# Sheet1.net
KiCad netlist of a schematic drawn in Altium Designer
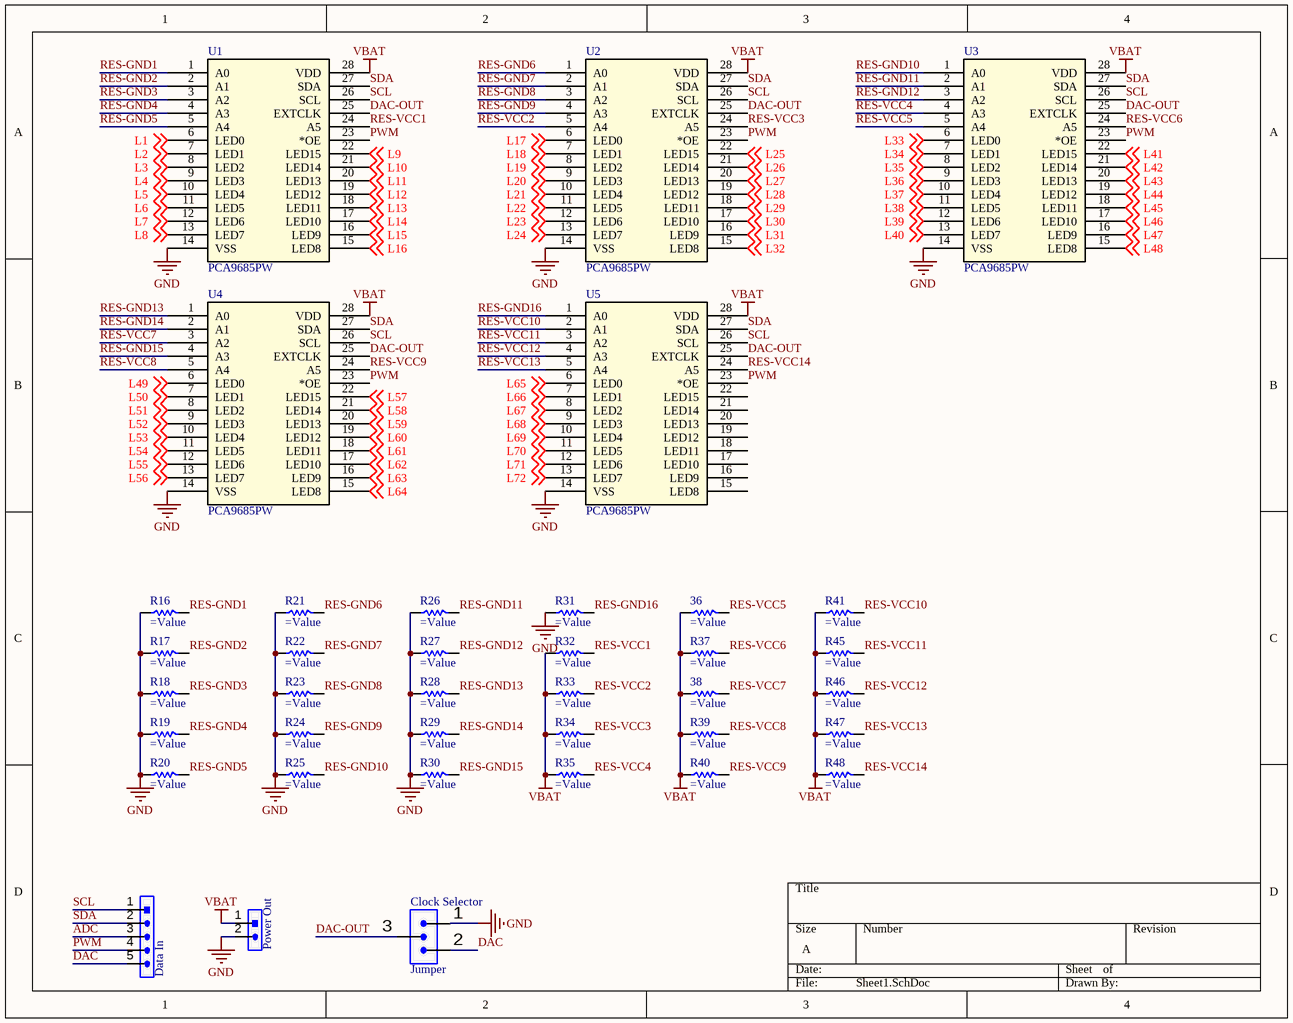
[diagram p0: Sheet1.SchDoc]

(export (version "E")
  (design (tool "Eeschema 10.0.6"))
  (components
    (comp (ref "36")
      (value "~")
      (footprint "R 0805")
      (description "Chip resistor")
      (fields (field (name "版权归属") "源创客"))
      (libsource (lib "Passive (Resistor-Capacitor-Inductor-Veristor-Ferrite)") (part "R"))
    )
    (comp (ref "38")
      (value "~")
      (footprint "R 0805")
      (description "Chip resistor")
      (fields (field (name "版权归属") "源创客"))
      (libsource (lib "Passive (Resistor-Capacitor-Inductor-Veristor-Ferrite)") (part "R"))
    )
    (comp (ref "Clock Selector")
      (value "Jumper")
      (footprint "Jumper Selector")
      (description "Jumper Selector")
      (libsource (lib "Jumper-SolderBridge") (part "Jumper Selector"))
    )
    (comp (ref "Data In")
      (value "HDR-1X5")
      (footprint "XH2.54-5P_H")
      (description "5P Connector")
      (fields (field (name "版权归属") "源创客"))
      (libsource (lib "Connectors") (part "Header 5"))
    )
    (comp (ref "Power Out")
      (value "HDR-1X2")
      (footprint "XH2.54-2P_H")
      (description "2P Connector")
      (fields (field (name "版权归属") "源创客"))
      (libsource (lib "Connectors") (part "Header 2"))
    )
    (comp (ref "R16")
      (value "~")
      (footprint "R 0805")
      (description "Chip resistor")
      (fields (field (name "版权归属") "源创客"))
      (libsource (lib "Passive (Resistor-Capacitor-Inductor-Veristor-Ferrite)") (part "R"))
    )
    (comp (ref "R17")
      (value "~")
      (footprint "R 0805")
      (description "Chip resistor")
      (fields (field (name "版权归属") "源创客"))
      (libsource (lib "Passive (Resistor-Capacitor-Inductor-Veristor-Ferrite)") (part "R"))
    )
    (comp (ref "R18")
      (value "~")
      (footprint "R 0805")
      (description "Chip resistor")
      (fields (field (name "版权归属") "源创客"))
      (libsource (lib "Passive (Resistor-Capacitor-Inductor-Veristor-Ferrite)") (part "R"))
    )
    (comp (ref "R19")
      (value "~")
      (footprint "R 0805")
      (description "Chip resistor")
      (fields (field (name "版权归属") "源创客"))
      (libsource (lib "Passive (Resistor-Capacitor-Inductor-Veristor-Ferrite)") (part "R"))
    )
    (comp (ref "R20")
      (value "~")
      (footprint "R 0805")
      (description "Chip resistor")
      (fields (field (name "版权归属") "源创客"))
      (libsource (lib "Passive (Resistor-Capacitor-Inductor-Veristor-Ferrite)") (part "R"))
    )
    (comp (ref "R21")
      (value "~")
      (footprint "R 0805")
      (description "Chip resistor")
      (fields (field (name "版权归属") "源创客"))
      (libsource (lib "Passive (Resistor-Capacitor-Inductor-Veristor-Ferrite)") (part "R"))
    )
    (comp (ref "R22")
      (value "~")
      (footprint "R 0805")
      (description "Chip resistor")
      (fields (field (name "版权归属") "源创客"))
      (libsource (lib "Passive (Resistor-Capacitor-Inductor-Veristor-Ferrite)") (part "R"))
    )
    (comp (ref "R23")
      (value "~")
      (footprint "R 0805")
      (description "Chip resistor")
      (fields (field (name "版权归属") "源创客"))
      (libsource (lib "Passive (Resistor-Capacitor-Inductor-Veristor-Ferrite)") (part "R"))
    )
    (comp (ref "R24")
      (value "~")
      (footprint "R 0805")
      (description "Chip resistor")
      (fields (field (name "版权归属") "源创客"))
      (libsource (lib "Passive (Resistor-Capacitor-Inductor-Veristor-Ferrite)") (part "R"))
    )
    (comp (ref "R25")
      (value "~")
      (footprint "R 0805")
      (description "Chip resistor")
      (fields (field (name "版权归属") "源创客"))
      (libsource (lib "Passive (Resistor-Capacitor-Inductor-Veristor-Ferrite)") (part "R"))
    )
    (comp (ref "R26")
      (value "~")
      (footprint "R 0805")
      (description "Chip resistor")
      (fields (field (name "版权归属") "源创客"))
      (libsource (lib "Passive (Resistor-Capacitor-Inductor-Veristor-Ferrite)") (part "R"))
    )
    (comp (ref "R27")
      (value "~")
      (footprint "R 0805")
      (description "Chip resistor")
      (fields (field (name "版权归属") "源创客"))
      (libsource (lib "Passive (Resistor-Capacitor-Inductor-Veristor-Ferrite)") (part "R"))
    )
    (comp (ref "R28")
      (value "~")
      (footprint "R 0805")
      (description "Chip resistor")
      (fields (field (name "版权归属") "源创客"))
      (libsource (lib "Passive (Resistor-Capacitor-Inductor-Veristor-Ferrite)") (part "R"))
    )
    (comp (ref "R29")
      (value "~")
      (footprint "R 0805")
      (description "Chip resistor")
      (fields (field (name "版权归属") "源创客"))
      (libsource (lib "Passive (Resistor-Capacitor-Inductor-Veristor-Ferrite)") (part "R"))
    )
    (comp (ref "R30")
      (value "~")
      (footprint "R 0805")
      (description "Chip resistor")
      (fields (field (name "版权归属") "源创客"))
      (libsource (lib "Passive (Resistor-Capacitor-Inductor-Veristor-Ferrite)") (part "R"))
    )
    (comp (ref "R31")
      (value "~")
      (footprint "R 0805")
      (description "Chip resistor")
      (fields (field (name "版权归属") "源创客"))
      (libsource (lib "Passive (Resistor-Capacitor-Inductor-Veristor-Ferrite)") (part "R"))
    )
    (comp (ref "R32")
      (value "~")
      (footprint "R 0805")
      (description "Chip resistor")
      (fields (field (name "版权归属") "源创客"))
      (libsource (lib "Passive (Resistor-Capacitor-Inductor-Veristor-Ferrite)") (part "R"))
    )
    (comp (ref "R33")
      (value "~")
      (footprint "R 0805")
      (description "Chip resistor")
      (fields (field (name "版权归属") "源创客"))
      (libsource (lib "Passive (Resistor-Capacitor-Inductor-Veristor-Ferrite)") (part "R"))
    )
    (comp (ref "R34")
      (value "~")
      (footprint "R 0805")
      (description "Chip resistor")
      (fields (field (name "版权归属") "源创客"))
      (libsource (lib "Passive (Resistor-Capacitor-Inductor-Veristor-Ferrite)") (part "R"))
    )
    (comp (ref "R35")
      (value "~")
      (footprint "R 0805")
      (description "Chip resistor")
      (fields (field (name "版权归属") "源创客"))
      (libsource (lib "Passive (Resistor-Capacitor-Inductor-Veristor-Ferrite)") (part "R"))
    )
    (comp (ref "R37")
      (value "~")
      (footprint "R 0805")
      (description "Chip resistor")
      (fields (field (name "版权归属") "源创客"))
      (libsource (lib "Passive (Resistor-Capacitor-Inductor-Veristor-Ferrite)") (part "R"))
    )
    (comp (ref "R39")
      (value "~")
      (footprint "R 0805")
      (description "Chip resistor")
      (fields (field (name "版权归属") "源创客"))
      (libsource (lib "Passive (Resistor-Capacitor-Inductor-Veristor-Ferrite)") (part "R"))
    )
    (comp (ref "R40")
      (value "~")
      (footprint "R 0805")
      (description "Chip resistor")
      (fields (field (name "版权归属") "源创客"))
      (libsource (lib "Passive (Resistor-Capacitor-Inductor-Veristor-Ferrite)") (part "R"))
    )
    (comp (ref "R41")
      (value "~")
      (footprint "R 0805")
      (description "Chip resistor")
      (fields (field (name "版权归属") "源创客"))
      (libsource (lib "Passive (Resistor-Capacitor-Inductor-Veristor-Ferrite)") (part "R"))
    )
    (comp (ref "R45")
      (value "~")
      (footprint "R 0805")
      (description "Chip resistor")
      (fields (field (name "版权归属") "源创客"))
      (libsource (lib "Passive (Resistor-Capacitor-Inductor-Veristor-Ferrite)") (part "R"))
    )
    (comp (ref "R46")
      (value "~")
      (footprint "R 0805")
      (description "Chip resistor")
      (fields (field (name "版权归属") "源创客"))
      (libsource (lib "Passive (Resistor-Capacitor-Inductor-Veristor-Ferrite)") (part "R"))
    )
    (comp (ref "R47")
      (value "~")
      (footprint "R 0805")
      (description "Chip resistor")
      (fields (field (name "版权归属") "源创客"))
      (libsource (lib "Passive (Resistor-Capacitor-Inductor-Veristor-Ferrite)") (part "R"))
    )
    (comp (ref "R48")
      (value "~")
      (footprint "R 0805")
      (description "Chip resistor")
      (fields (field (name "版权归属") "源创客"))
      (libsource (lib "Passive (Resistor-Capacitor-Inductor-Veristor-Ferrite)") (part "R"))
    )
    (comp (ref "U1")
      (value "PCA9685PW")
      (footprint "SOT361-1_NXP")
      (description "No Description Available")
      (fields (field (name "COPYRIGHT") "Copyright (C) 2018 Accelerated Designs. All rights reserved"))
      (libsource (lib "PCA9685") (part "PCA9685PW"))
    )
    (comp (ref "U2")
      (value "PCA9685PW")
      (footprint "SOT361-1_NXP")
      (description "No Description Available")
      (fields (field (name "COPYRIGHT") "Copyright (C) 2018 Accelerated Designs. All rights reserved"))
      (libsource (lib "PCA9685") (part "PCA9685PW"))
    )
    (comp (ref "U3")
      (value "PCA9685PW")
      (footprint "SOT361-1_NXP")
      (description "No Description Available")
      (fields (field (name "COPYRIGHT") "Copyright (C) 2018 Accelerated Designs. All rights reserved"))
      (libsource (lib "PCA9685") (part "PCA9685PW"))
    )
    (comp (ref "U4")
      (value "PCA9685PW")
      (footprint "SOT361-1_NXP")
      (description "No Description Available")
      (fields (field (name "COPYRIGHT") "Copyright (C) 2018 Accelerated Designs. All rights reserved"))
      (libsource (lib "PCA9685") (part "PCA9685PW"))
    )
    (comp (ref "U5")
      (value "PCA9685PW")
      (footprint "SOT361-1_NXP")
      (description "No Description Available")
      (fields (field (name "COPYRIGHT") "Copyright (C) 2018 Accelerated Designs. All rights reserved"))
      (libsource (lib "PCA9685") (part "PCA9685PW"))
    )
  )
  (nets
    (net (code "1") (name "/ADC") (class "Default") (node (ref "Data In") (pin "3") (pintype "passive")))
    (net (code "2") (name "/DAC") (class "Default") (node (ref "Data In") (pin "5") (pintype "passive")))
    (net (code "3") (name "/DAC-OUT") (class "Default")
      (node (ref "Clock Selector") (pin "3") (pinfunction "IN_3") (pintype "passive"))
      (node (ref "U1") (pin "25") (pinfunction "EXTCLK_25") (pintype "passive"))
      (node (ref "U2") (pin "25") (pinfunction "EXTCLK_25") (pintype "passive"))
      (node (ref "U3") (pin "25") (pinfunction "EXTCLK_25") (pintype "passive"))
      (node (ref "U4") (pin "25") (pinfunction "EXTCLK_25") (pintype "passive"))
      (node (ref "U5") (pin "25") (pinfunction "EXTCLK_25") (pintype "passive"))
    )
    (net (code "4") (name "/PWM") (class "Default")
      (node (ref "Data In") (pin "4") (pintype "passive"))
      (node (ref "U1") (pin "23") (pinfunction "*OE_23") (pintype "passive"))
      (node (ref "U2") (pin "23") (pinfunction "*OE_23") (pintype "passive"))
      (node (ref "U3") (pin "23") (pinfunction "*OE_23") (pintype "passive"))
      (node (ref "U4") (pin "23") (pinfunction "*OE_23") (pintype "passive"))
      (node (ref "U5") (pin "23") (pinfunction "*OE_23") (pintype "passive"))
    )
    (net (code "5") (name "/RES-GND1") (class "Default")
      (node (ref "R16") (pin "2") (pinfunction "2_2") (pintype "passive"))
      (node (ref "U1") (pin "1") (pinfunction "A0_1") (pintype "passive"))
    )
    (net (code "6") (name "/RES-GND2") (class "Default")
      (node (ref "R17") (pin "2") (pinfunction "2_2") (pintype "passive"))
      (node (ref "U1") (pin "2") (pinfunction "A1_2") (pintype "passive"))
    )
    (net (code "7") (name "/RES-GND3") (class "Default")
      (node (ref "R18") (pin "2") (pinfunction "2_2") (pintype "passive"))
      (node (ref "U1") (pin "3") (pinfunction "A2_3") (pintype "passive"))
    )
    (net (code "8") (name "/RES-GND4") (class "Default")
      (node (ref "R19") (pin "2") (pinfunction "2_2") (pintype "passive"))
      (node (ref "U1") (pin "4") (pinfunction "A3_4") (pintype "passive"))
    )
    (net (code "9") (name "/RES-GND5") (class "Default")
      (node (ref "R20") (pin "2") (pinfunction "2_2") (pintype "passive"))
      (node (ref "U1") (pin "5") (pinfunction "A4_5") (pintype "passive"))
    )
    (net (code "10") (name "/RES-GND6") (class "Default")
      (node (ref "R21") (pin "2") (pinfunction "2_2") (pintype "passive"))
      (node (ref "U2") (pin "1") (pinfunction "A0_1") (pintype "passive"))
    )
    (net (code "11") (name "/RES-GND7") (class "Default")
      (node (ref "R22") (pin "2") (pinfunction "2_2") (pintype "passive"))
      (node (ref "U2") (pin "2") (pinfunction "A1_2") (pintype "passive"))
    )
    (net (code "12") (name "/RES-GND8") (class "Default")
      (node (ref "R23") (pin "2") (pinfunction "2_2") (pintype "passive"))
      (node (ref "U2") (pin "3") (pinfunction "A2_3") (pintype "passive"))
    )
    (net (code "13") (name "/RES-GND9") (class "Default")
      (node (ref "R24") (pin "2") (pinfunction "2_2") (pintype "passive"))
      (node (ref "U2") (pin "4") (pinfunction "A3_4") (pintype "passive"))
    )
    (net (code "14") (name "/RES-GND10") (class "Default")
      (node (ref "R25") (pin "2") (pinfunction "2_2") (pintype "passive"))
      (node (ref "U3") (pin "1") (pinfunction "A0_1") (pintype "passive"))
    )
    (net (code "15") (name "/RES-GND11") (class "Default")
      (node (ref "R26") (pin "2") (pinfunction "2_2") (pintype "passive"))
      (node (ref "U3") (pin "2") (pinfunction "A1_2") (pintype "passive"))
    )
    (net (code "16") (name "/RES-GND12") (class "Default")
      (node (ref "R27") (pin "2") (pinfunction "2_2") (pintype "passive"))
      (node (ref "U3") (pin "3") (pinfunction "A2_3") (pintype "passive"))
    )
    (net (code "17") (name "/RES-GND13") (class "Default")
      (node (ref "R28") (pin "2") (pinfunction "2_2") (pintype "passive"))
      (node (ref "U4") (pin "1") (pinfunction "A0_1") (pintype "passive"))
    )
    (net (code "18") (name "/RES-GND14") (class "Default")
      (node (ref "R29") (pin "2") (pinfunction "2_2") (pintype "passive"))
      (node (ref "U4") (pin "2") (pinfunction "A1_2") (pintype "passive"))
    )
    (net (code "19") (name "/RES-GND15") (class "Default")
      (node (ref "R30") (pin "2") (pinfunction "2_2") (pintype "passive"))
      (node (ref "U4") (pin "4") (pinfunction "A3_4") (pintype "passive"))
    )
    (net (code "20") (name "/RES-GND16") (class "Default")
      (node (ref "R31") (pin "2") (pinfunction "2_2") (pintype "passive"))
      (node (ref "U5") (pin "1") (pinfunction "A0_1") (pintype "passive"))
    )
    (net (code "21") (name "/RES-VCC1") (class "Default")
      (node (ref "R32") (pin "2") (pinfunction "2_2") (pintype "passive"))
      (node (ref "U1") (pin "24") (pinfunction "A5_24") (pintype "passive"))
    )
    (net (code "22") (name "/RES-VCC2") (class "Default")
      (node (ref "R33") (pin "2") (pinfunction "2_2") (pintype "passive"))
      (node (ref "U2") (pin "5") (pinfunction "A4_5") (pintype "passive"))
    )
    (net (code "23") (name "/RES-VCC3") (class "Default")
      (node (ref "R34") (pin "2") (pinfunction "2_2") (pintype "passive"))
      (node (ref "U2") (pin "24") (pinfunction "A5_24") (pintype "passive"))
    )
    (net (code "24") (name "/RES-VCC4") (class "Default")
      (node (ref "R35") (pin "2") (pinfunction "2_2") (pintype "passive"))
      (node (ref "U3") (pin "4") (pinfunction "A3_4") (pintype "passive"))
    )
    (net (code "25") (name "/RES-VCC5") (class "Default")
      (node (ref "36") (pin "2") (pinfunction "2_2") (pintype "passive"))
      (node (ref "U3") (pin "5") (pinfunction "A4_5") (pintype "passive"))
    )
    (net (code "26") (name "/RES-VCC6") (class "Default")
      (node (ref "R37") (pin "2") (pinfunction "2_2") (pintype "passive"))
      (node (ref "U3") (pin "24") (pinfunction "A5_24") (pintype "passive"))
    )
    (net (code "27") (name "/RES-VCC7") (class "Default")
      (node (ref "38") (pin "2") (pinfunction "2_2") (pintype "passive"))
      (node (ref "U4") (pin "3") (pinfunction "A2_3") (pintype "passive"))
    )
    (net (code "28") (name "/RES-VCC8") (class "Default")
      (node (ref "R39") (pin "2") (pinfunction "2_2") (pintype "passive"))
      (node (ref "U4") (pin "5") (pinfunction "A4_5") (pintype "passive"))
    )
    (net (code "29") (name "/RES-VCC9") (class "Default")
      (node (ref "R40") (pin "2") (pinfunction "2_2") (pintype "passive"))
      (node (ref "U4") (pin "24") (pinfunction "A5_24") (pintype "passive"))
    )
    (net (code "30") (name "/RES-VCC10") (class "Default")
      (node (ref "R41") (pin "2") (pinfunction "2_2") (pintype "passive"))
      (node (ref "U5") (pin "2") (pinfunction "A1_2") (pintype "passive"))
    )
    (net (code "31") (name "/RES-VCC11") (class "Default")
      (node (ref "R45") (pin "2") (pinfunction "2_2") (pintype "passive"))
      (node (ref "U5") (pin "3") (pinfunction "A2_3") (pintype "passive"))
    )
    (net (code "32") (name "/RES-VCC12") (class "Default")
      (node (ref "R46") (pin "2") (pinfunction "2_2") (pintype "passive"))
      (node (ref "U5") (pin "4") (pinfunction "A3_4") (pintype "passive"))
    )
    (net (code "33") (name "/RES-VCC13") (class "Default")
      (node (ref "R47") (pin "2") (pinfunction "2_2") (pintype "passive"))
      (node (ref "U5") (pin "5") (pinfunction "A4_5") (pintype "passive"))
    )
    (net (code "34") (name "/RES-VCC14") (class "Default")
      (node (ref "R48") (pin "2") (pinfunction "2_2") (pintype "passive"))
      (node (ref "U5") (pin "24") (pinfunction "A5_24") (pintype "passive"))
    )
    (net (code "35") (name "/SCL") (class "Default")
      (node (ref "Data In") (pin "1") (pintype "passive"))
      (node (ref "U1") (pin "26") (pinfunction "SCL_26") (pintype "passive"))
      (node (ref "U2") (pin "26") (pinfunction "SCL_26") (pintype "passive"))
      (node (ref "U3") (pin "26") (pinfunction "SCL_26") (pintype "passive"))
      (node (ref "U4") (pin "26") (pinfunction "SCL_26") (pintype "passive"))
      (node (ref "U5") (pin "26") (pinfunction "SCL_26") (pintype "passive"))
    )
    (net (code "36") (name "/SDA") (class "Default")
      (node (ref "Data In") (pin "2") (pintype "passive"))
      (node (ref "U1") (pin "27") (pinfunction "SDA_27") (pintype "passive"))
      (node (ref "U2") (pin "27") (pinfunction "SDA_27") (pintype "passive"))
      (node (ref "U3") (pin "27") (pinfunction "SDA_27") (pintype "passive"))
      (node (ref "U4") (pin "27") (pinfunction "SDA_27") (pintype "passive"))
      (node (ref "U5") (pin "27") (pinfunction "SDA_27") (pintype "passive"))
    )
    (net (code "37") (name "GND") (class "Default")
      (node (ref "Clock Selector") (pin "1") (pinfunction "IN_1") (pintype "passive"))
      (node (ref "Power Out") (pin "2") (pintype "passive"))
      (node (ref "R16") (pin "1") (pinfunction "1_1") (pintype "passive"))
      (node (ref "R17") (pin "1") (pinfunction "1_1") (pintype "passive"))
      (node (ref "R18") (pin "1") (pinfunction "1_1") (pintype "passive"))
      (node (ref "R19") (pin "1") (pinfunction "1_1") (pintype "passive"))
      (node (ref "R20") (pin "1") (pinfunction "1_1") (pintype "passive"))
      (node (ref "R21") (pin "1") (pinfunction "1_1") (pintype "passive"))
      (node (ref "R22") (pin "1") (pinfunction "1_1") (pintype "passive"))
      (node (ref "R23") (pin "1") (pinfunction "1_1") (pintype "passive"))
      (node (ref "R24") (pin "1") (pinfunction "1_1") (pintype "passive"))
      (node (ref "R25") (pin "1") (pinfunction "1_1") (pintype "passive"))
      (node (ref "R26") (pin "1") (pinfunction "1_1") (pintype "passive"))
      (node (ref "R27") (pin "1") (pinfunction "1_1") (pintype "passive"))
      (node (ref "R28") (pin "1") (pinfunction "1_1") (pintype "passive"))
      (node (ref "R29") (pin "1") (pinfunction "1_1") (pintype "passive"))
      (node (ref "R30") (pin "1") (pinfunction "1_1") (pintype "passive"))
      (node (ref "R31") (pin "1") (pinfunction "1_1") (pintype "passive"))
      (node (ref "U1") (pin "14") (pinfunction "VSS_14") (pintype "passive"))
      (node (ref "U2") (pin "14") (pinfunction "VSS_14") (pintype "passive"))
      (node (ref "U3") (pin "14") (pinfunction "VSS_14") (pintype "passive"))
      (node (ref "U4") (pin "14") (pinfunction "VSS_14") (pintype "passive"))
      (node (ref "U5") (pin "14") (pinfunction "VSS_14") (pintype "passive"))
    )
    (net (code "38") (name "L1") (class "Default")
      (node (ref "U1") (pin "6") (pinfunction "LED0_6") (pintype "passive"))
    )
    (net (code "39") (name "L2") (class "Default")
      (node (ref "U1") (pin "7") (pinfunction "LED1_7") (pintype "passive"))
    )
    (net (code "40") (name "L3") (class "Default")
      (node (ref "U1") (pin "8") (pinfunction "LED2_8") (pintype "passive"))
    )
    (net (code "41") (name "L4") (class "Default")
      (node (ref "U1") (pin "9") (pinfunction "LED3_9") (pintype "passive"))
    )
    (net (code "42") (name "L5") (class "Default")
      (node (ref "U1") (pin "10") (pinfunction "LED4_10") (pintype "passive"))
    )
    (net (code "43") (name "L6") (class "Default")
      (node (ref "U1") (pin "11") (pinfunction "LED5_11") (pintype "passive"))
    )
    (net (code "44") (name "L7") (class "Default")
      (node (ref "U1") (pin "12") (pinfunction "LED6_12") (pintype "passive"))
    )
    (net (code "45") (name "L8") (class "Default")
      (node (ref "U1") (pin "13") (pinfunction "LED7_13") (pintype "passive"))
    )
    (net (code "46") (name "L9") (class "Default")
      (node (ref "U1") (pin "22") (pinfunction "LED15_22") (pintype "passive"))
    )
    (net (code "47") (name "L10") (class "Default")
      (node (ref "U1") (pin "21") (pinfunction "LED14_21") (pintype "passive"))
    )
    (net (code "48") (name "L11") (class "Default")
      (node (ref "U1") (pin "20") (pinfunction "LED13_20") (pintype "passive"))
    )
    (net (code "49") (name "L12") (class "Default")
      (node (ref "U1") (pin "19") (pinfunction "LED12_19") (pintype "passive"))
    )
    (net (code "50") (name "L13") (class "Default")
      (node (ref "U1") (pin "18") (pinfunction "LED11_18") (pintype "passive"))
    )
    (net (code "51") (name "L14") (class "Default")
      (node (ref "U1") (pin "17") (pinfunction "LED10_17") (pintype "passive"))
    )
    (net (code "52") (name "L15") (class "Default")
      (node (ref "U1") (pin "16") (pinfunction "LED9_16") (pintype "passive"))
    )
    (net (code "53") (name "L16") (class "Default")
      (node (ref "U1") (pin "15") (pinfunction "LED8_15") (pintype "passive"))
    )
    (net (code "54") (name "L17") (class "Default")
      (node (ref "U2") (pin "6") (pinfunction "LED0_6") (pintype "passive"))
    )
    (net (code "55") (name "L18") (class "Default")
      (node (ref "U2") (pin "7") (pinfunction "LED1_7") (pintype "passive"))
    )
    (net (code "56") (name "L19") (class "Default")
      (node (ref "U2") (pin "8") (pinfunction "LED2_8") (pintype "passive"))
    )
    (net (code "57") (name "L20") (class "Default")
      (node (ref "U2") (pin "9") (pinfunction "LED3_9") (pintype "passive"))
    )
    (net (code "58") (name "L21") (class "Default")
      (node (ref "U2") (pin "10") (pinfunction "LED4_10") (pintype "passive"))
    )
    (net (code "59") (name "L22") (class "Default")
      (node (ref "U2") (pin "11") (pinfunction "LED5_11") (pintype "passive"))
    )
    (net (code "60") (name "L23") (class "Default")
      (node (ref "U2") (pin "12") (pinfunction "LED6_12") (pintype "passive"))
    )
    (net (code "61") (name "L24") (class "Default")
      (node (ref "U2") (pin "13") (pinfunction "LED7_13") (pintype "passive"))
    )
    (net (code "62") (name "L25") (class "Default")
      (node (ref "U2") (pin "22") (pinfunction "LED15_22") (pintype "passive"))
    )
    (net (code "63") (name "L26") (class "Default")
      (node (ref "U2") (pin "21") (pinfunction "LED14_21") (pintype "passive"))
    )
    (net (code "64") (name "L27") (class "Default")
      (node (ref "U2") (pin "20") (pinfunction "LED13_20") (pintype "passive"))
    )
    (net (code "65") (name "L28") (class "Default")
      (node (ref "U2") (pin "19") (pinfunction "LED12_19") (pintype "passive"))
    )
    (net (code "66") (name "L29") (class "Default")
      (node (ref "U2") (pin "18") (pinfunction "LED11_18") (pintype "passive"))
    )
    (net (code "67") (name "L30") (class "Default")
      (node (ref "U2") (pin "17") (pinfunction "LED10_17") (pintype "passive"))
    )
    (net (code "68") (name "L31") (class "Default")
      (node (ref "U2") (pin "16") (pinfunction "LED9_16") (pintype "passive"))
    )
    (net (code "69") (name "L32") (class "Default")
      (node (ref "U2") (pin "15") (pinfunction "LED8_15") (pintype "passive"))
    )
    (net (code "70") (name "L33") (class "Default")
      (node (ref "U3") (pin "6") (pinfunction "LED0_6") (pintype "passive"))
    )
    (net (code "71") (name "L34") (class "Default")
      (node (ref "U3") (pin "7") (pinfunction "LED1_7") (pintype "passive"))
    )
    (net (code "72") (name "L35") (class "Default")
      (node (ref "U3") (pin "8") (pinfunction "LED2_8") (pintype "passive"))
    )
    (net (code "73") (name "L36") (class "Default")
      (node (ref "U3") (pin "9") (pinfunction "LED3_9") (pintype "passive"))
    )
    (net (code "74") (name "L37") (class "Default")
      (node (ref "U3") (pin "10") (pinfunction "LED4_10") (pintype "passive"))
    )
    (net (code "75") (name "L38") (class "Default")
      (node (ref "U3") (pin "11") (pinfunction "LED5_11") (pintype "passive"))
    )
    (net (code "76") (name "L39") (class "Default")
      (node (ref "U3") (pin "12") (pinfunction "LED6_12") (pintype "passive"))
    )
    (net (code "77") (name "L40") (class "Default")
      (node (ref "U3") (pin "13") (pinfunction "LED7_13") (pintype "passive"))
    )
    (net (code "78") (name "L41") (class "Default")
      (node (ref "U3") (pin "22") (pinfunction "LED15_22") (pintype "passive"))
    )
    (net (code "79") (name "L42") (class "Default")
      (node (ref "U3") (pin "21") (pinfunction "LED14_21") (pintype "passive"))
    )
    (net (code "80") (name "L43") (class "Default")
      (node (ref "U3") (pin "20") (pinfunction "LED13_20") (pintype "passive"))
    )
    (net (code "81") (name "L44") (class "Default")
      (node (ref "U3") (pin "19") (pinfunction "LED12_19") (pintype "passive"))
    )
    (net (code "82") (name "L45") (class "Default")
      (node (ref "U3") (pin "18") (pinfunction "LED11_18") (pintype "passive"))
    )
    (net (code "83") (name "L46") (class "Default")
      (node (ref "U3") (pin "17") (pinfunction "LED10_17") (pintype "passive"))
    )
    (net (code "84") (name "L47") (class "Default")
      (node (ref "U3") (pin "16") (pinfunction "LED9_16") (pintype "passive"))
    )
    (net (code "85") (name "L48") (class "Default")
      (node (ref "U3") (pin "15") (pinfunction "LED8_15") (pintype "passive"))
    )
    (net (code "86") (name "L49") (class "Default")
      (node (ref "U4") (pin "6") (pinfunction "LED0_6") (pintype "passive"))
    )
    (net (code "87") (name "L50") (class "Default")
      (node (ref "U4") (pin "7") (pinfunction "LED1_7") (pintype "passive"))
    )
    (net (code "88") (name "L51") (class "Default")
      (node (ref "U4") (pin "8") (pinfunction "LED2_8") (pintype "passive"))
    )
    (net (code "89") (name "L52") (class "Default")
      (node (ref "U4") (pin "9") (pinfunction "LED3_9") (pintype "passive"))
    )
    (net (code "90") (name "L53") (class "Default")
      (node (ref "U4") (pin "10") (pinfunction "LED4_10") (pintype "passive"))
    )
    (net (code "91") (name "L54") (class "Default")
      (node (ref "U4") (pin "11") (pinfunction "LED5_11") (pintype "passive"))
    )
    (net (code "92") (name "L55") (class "Default")
      (node (ref "U4") (pin "12") (pinfunction "LED6_12") (pintype "passive"))
    )
    (net (code "93") (name "L56") (class "Default")
      (node (ref "U4") (pin "13") (pinfunction "LED7_13") (pintype "passive"))
    )
    (net (code "94") (name "L57") (class "Default")
      (node (ref "U4") (pin "22") (pinfunction "LED15_22") (pintype "passive"))
    )
    (net (code "95") (name "L58") (class "Default")
      (node (ref "U4") (pin "21") (pinfunction "LED14_21") (pintype "passive"))
    )
    (net (code "96") (name "L59") (class "Default")
      (node (ref "U4") (pin "20") (pinfunction "LED13_20") (pintype "passive"))
    )
    (net (code "97") (name "L60") (class "Default")
      (node (ref "U4") (pin "19") (pinfunction "LED12_19") (pintype "passive"))
    )
    (net (code "98") (name "L61") (class "Default")
      (node (ref "U4") (pin "18") (pinfunction "LED11_18") (pintype "passive"))
    )
    (net (code "99") (name "L62") (class "Default")
      (node (ref "U4") (pin "17") (pinfunction "LED10_17") (pintype "passive"))
    )
    (net (code "100") (name "L63") (class "Default")
      (node (ref "U4") (pin "16") (pinfunction "LED9_16") (pintype "passive"))
    )
    (net (code "101") (name "L64") (class "Default")
      (node (ref "U4") (pin "15") (pinfunction "LED8_15") (pintype "passive"))
    )
    (net (code "102") (name "L65") (class "Default")
      (node (ref "U5") (pin "6") (pinfunction "LED0_6") (pintype "passive"))
    )
    (net (code "103") (name "L66") (class "Default")
      (node (ref "U5") (pin "7") (pinfunction "LED1_7") (pintype "passive"))
    )
    (net (code "104") (name "L67") (class "Default")
      (node (ref "U5") (pin "8") (pinfunction "LED2_8") (pintype "passive"))
    )
    (net (code "105") (name "L68") (class "Default")
      (node (ref "U5") (pin "9") (pinfunction "LED3_9") (pintype "passive"))
    )
    (net (code "106") (name "L69") (class "Default")
      (node (ref "U5") (pin "10") (pinfunction "LED4_10") (pintype "passive"))
    )
    (net (code "107") (name "L70") (class "Default")
      (node (ref "U5") (pin "11") (pinfunction "LED5_11") (pintype "passive"))
    )
    (net (code "108") (name "L71") (class "Default")
      (node (ref "U5") (pin "12") (pinfunction "LED6_12") (pintype "passive"))
    )
    (net (code "109") (name "L72") (class "Default")
      (node (ref "U5") (pin "13") (pinfunction "LED7_13") (pintype "passive"))
    )
    (net (code "110") (name "VBAT") (class "Default")
      (node (ref "36") (pin "1") (pinfunction "1_1") (pintype "passive"))
      (node (ref "38") (pin "1") (pinfunction "1_1") (pintype "passive"))
      (node (ref "Power Out") (pin "1") (pintype "passive"))
      (node (ref "R32") (pin "1") (pinfunction "1_1") (pintype "passive"))
      (node (ref "R33") (pin "1") (pinfunction "1_1") (pintype "passive"))
      (node (ref "R34") (pin "1") (pinfunction "1_1") (pintype "passive"))
      (node (ref "R35") (pin "1") (pinfunction "1_1") (pintype "passive"))
      (node (ref "R37") (pin "1") (pinfunction "1_1") (pintype "passive"))
      (node (ref "R39") (pin "1") (pinfunction "1_1") (pintype "passive"))
      (node (ref "R40") (pin "1") (pinfunction "1_1") (pintype "passive"))
      (node (ref "R41") (pin "1") (pinfunction "1_1") (pintype "passive"))
      (node (ref "R45") (pin "1") (pinfunction "1_1") (pintype "passive"))
      (node (ref "R46") (pin "1") (pinfunction "1_1") (pintype "passive"))
      (node (ref "R47") (pin "1") (pinfunction "1_1") (pintype "passive"))
      (node (ref "R48") (pin "1") (pinfunction "1_1") (pintype "passive"))
      (node (ref "U1") (pin "28") (pinfunction "VDD_28") (pintype "passive"))
      (node (ref "U2") (pin "28") (pinfunction "VDD_28") (pintype "passive"))
      (node (ref "U3") (pin "28") (pinfunction "VDD_28") (pintype "passive"))
      (node (ref "U4") (pin "28") (pinfunction "VDD_28") (pintype "passive"))
      (node (ref "U5") (pin "28") (pinfunction "VDD_28") (pintype "passive"))
    )
    (net (code "111") (name "unconnected-(Clock Selector-IN-Pad2)") (class "Default")
      (node (ref "Clock Selector") (pin "2") (pinfunction "IN_2") (pintype "passive"))
    )
    (net (code "112") (name "unconnected-(U5-LED8-Pad15)") (class "Default")
      (node (ref "U5") (pin "15") (pinfunction "LED8_15") (pintype "passive"))
    )
    (net (code "113") (name "unconnected-(U5-LED9-Pad16)") (class "Default")
      (node (ref "U5") (pin "16") (pinfunction "LED9_16") (pintype "passive"))
    )
    (net (code "114") (name "unconnected-(U5-LED10-Pad17)") (class "Default")
      (node (ref "U5") (pin "17") (pinfunction "LED10_17") (pintype "passive"))
    )
    (net (code "115") (name "unconnected-(U5-LED11-Pad18)") (class "Default")
      (node (ref "U5") (pin "18") (pinfunction "LED11_18") (pintype "passive"))
    )
    (net (code "116") (name "unconnected-(U5-LED12-Pad19)") (class "Default")
      (node (ref "U5") (pin "19") (pinfunction "LED12_19") (pintype "passive"))
    )
    (net (code "117") (name "unconnected-(U5-LED13-Pad20)") (class "Default")
      (node (ref "U5") (pin "20") (pinfunction "LED13_20") (pintype "passive"))
    )
    (net (code "118") (name "unconnected-(U5-LED14-Pad21)") (class "Default")
      (node (ref "U5") (pin "21") (pinfunction "LED14_21") (pintype "passive"))
    )
    (net (code "119") (name "unconnected-(U5-LED15-Pad22)") (class "Default")
      (node (ref "U5") (pin "22") (pinfunction "LED15_22") (pintype "passive"))
    )
  )
)
